# tyre_temps.net
KiCad netlist of a schematic drawn in Altium Designer
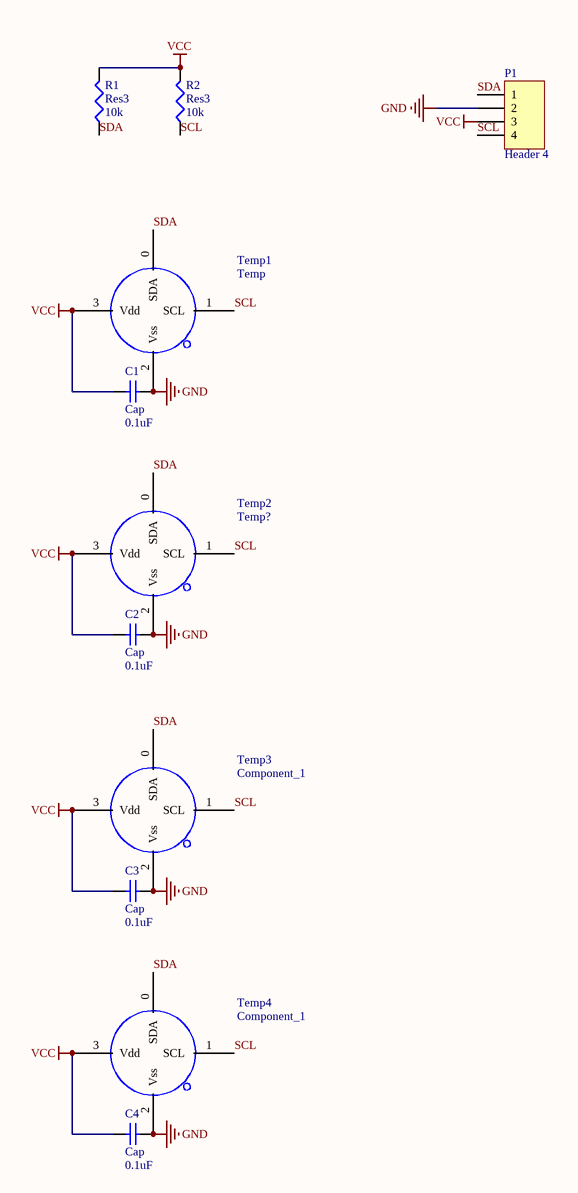
[diagram p0: tyre_temps.SchDoc]

(export (version "E")
  (design (tool "Eeschema 10.0.6"))
  (components
    (comp (ref "C1")
      (value "Cap")
      (footprint "R0805")
      (description "Capacitor")
      (fields (field (name "ALTIUM_VALUE") "0.1uF") (field (name "PUBLISHER") "Altium Limited"))
      (libsource (lib "Miscellaneous Devices") (part "Cap"))
    )
    (comp (ref "C2")
      (value "Cap")
      (footprint "R0805")
      (description "Capacitor")
      (fields (field (name "ALTIUM_VALUE") "0.1uF") (field (name "PUBLISHER") "Altium Limited"))
      (libsource (lib "Miscellaneous Devices") (part "Cap"))
    )
    (comp (ref "C3")
      (value "Cap")
      (footprint "R0805")
      (description "Capacitor")
      (fields (field (name "ALTIUM_VALUE") "0.1uF") (field (name "PUBLISHER") "Altium Limited"))
      (libsource (lib "Miscellaneous Devices") (part "Cap"))
    )
    (comp (ref "C4")
      (value "Cap")
      (footprint "R0805")
      (description "Capacitor")
      (fields (field (name "ALTIUM_VALUE") "0.1uF") (field (name "PUBLISHER") "Altium Limited"))
      (libsource (lib "Miscellaneous Devices") (part "Cap"))
    )
    (comp (ref "P1")
      (value "Header 4")
      (footprint "HDR1X4")
      (description "Header, 4-Pin")
      (fields (field (name "PUBLISHER") "Altium Limited"))
      (libsource (lib "Miscellaneous Connectors") (part "Header 4"))
    )
    (comp (ref "R1")
      (value "Res3")
      (footprint "R0805")
      (description "Resistor")
      (fields (field (name "ALTIUM_VALUE") "10k") (field (name "PUBLISHER") "Altium Limited"))
      (libsource (lib "Miscellaneous Devices") (part "Res3"))
    )
    (comp (ref "R2")
      (value "Res3")
      (footprint "R0805")
      (description "Resistor")
      (fields (field (name "ALTIUM_VALUE") "10k") (field (name "PUBLISHER") "Altium Limited"))
      (libsource (lib "Miscellaneous Devices") (part "Res3"))
    )
    (comp (ref "Temp1")
      (value "Temp")
      (footprint "MLX90614")
      (libsource (lib "MLX90614ESFACA") (part "Temp"))
    )
    (comp (ref "Temp2")
      (value "Temp?")
      (footprint "MLX90614")
      (libsource (lib "MLX90614ESFACA") (part "Temp?"))
    )
    (comp (ref "Temp3")
      (value "Component_1")
      (footprint "MLX90614")
      (libsource (lib "MLX90614ESFACA") (part "Component_1"))
    )
    (comp (ref "Temp4")
      (value "Component_1")
      (footprint "MLX90614")
      (libsource (lib "MLX90614ESFACA") (part "Component_1"))
    )
  )
  (nets
    (net (code "1") (name "/SCL") (class "Default")
      (node (ref "P1") (pin "4") (pinfunction "4_4") (pintype "passive"))
      (node (ref "R2") (pin "1") (pinfunction "1_1") (pintype "passive"))
      (node (ref "Temp1") (pin "1") (pinfunction "SCL_1") (pintype "passive"))
      (node (ref "Temp2") (pin "1") (pinfunction "SCL_1") (pintype "passive"))
      (node (ref "Temp3") (pin "1") (pinfunction "SCL_1") (pintype "passive"))
      (node (ref "Temp4") (pin "1") (pinfunction "SCL_1") (pintype "passive"))
    )
    (net (code "2") (name "/SDA") (class "Default")
      (node (ref "P1") (pin "1") (pinfunction "1_1") (pintype "passive"))
      (node (ref "R1") (pin "1") (pinfunction "1_1") (pintype "passive"))
      (node (ref "Temp1") (pin "0") (pinfunction "SDA_0") (pintype "passive"))
      (node (ref "Temp2") (pin "0") (pinfunction "SDA_0") (pintype "passive"))
      (node (ref "Temp3") (pin "0") (pinfunction "SDA_0") (pintype "passive"))
      (node (ref "Temp4") (pin "0") (pinfunction "SDA_0") (pintype "passive"))
    )
    (net (code "3") (name "GND") (class "Default")
      (node (ref "C1") (pin "2") (pinfunction "2_2") (pintype "passive"))
      (node (ref "C2") (pin "2") (pinfunction "2_2") (pintype "passive"))
      (node (ref "C3") (pin "2") (pinfunction "2_2") (pintype "passive"))
      (node (ref "C4") (pin "2") (pinfunction "2_2") (pintype "passive"))
      (node (ref "P1") (pin "2") (pinfunction "2_2") (pintype "passive"))
      (node (ref "Temp1") (pin "2") (pinfunction "Vss_2") (pintype "power_in"))
      (node (ref "Temp2") (pin "2") (pinfunction "Vss_2") (pintype "power_in"))
      (node (ref "Temp3") (pin "2") (pinfunction "Vss_2") (pintype "power_in"))
      (node (ref "Temp4") (pin "2") (pinfunction "Vss_2") (pintype "power_in"))
    )
    (net (code "4") (name "VCC") (class "Default")
      (node (ref "C1") (pin "1") (pinfunction "1_1") (pintype "passive"))
      (node (ref "C2") (pin "1") (pinfunction "1_1") (pintype "passive"))
      (node (ref "C3") (pin "1") (pinfunction "1_1") (pintype "passive"))
      (node (ref "C4") (pin "1") (pinfunction "1_1") (pintype "passive"))
      (node (ref "P1") (pin "3") (pinfunction "3_3") (pintype "passive"))
      (node (ref "R1") (pin "2") (pinfunction "2_2") (pintype "passive"))
      (node (ref "R2") (pin "2") (pinfunction "2_2") (pintype "passive"))
      (node (ref "Temp1") (pin "3") (pinfunction "Vdd_3") (pintype "power_in"))
      (node (ref "Temp2") (pin "3") (pinfunction "Vdd_3") (pintype "power_in"))
      (node (ref "Temp3") (pin "3") (pinfunction "Vdd_3") (pintype "power_in"))
      (node (ref "Temp4") (pin "3") (pinfunction "Vdd_3") (pintype "power_in"))
    )
  )
)
